# mother_card_10.net
KiCad netlist of a schematic drawn in EAGLE
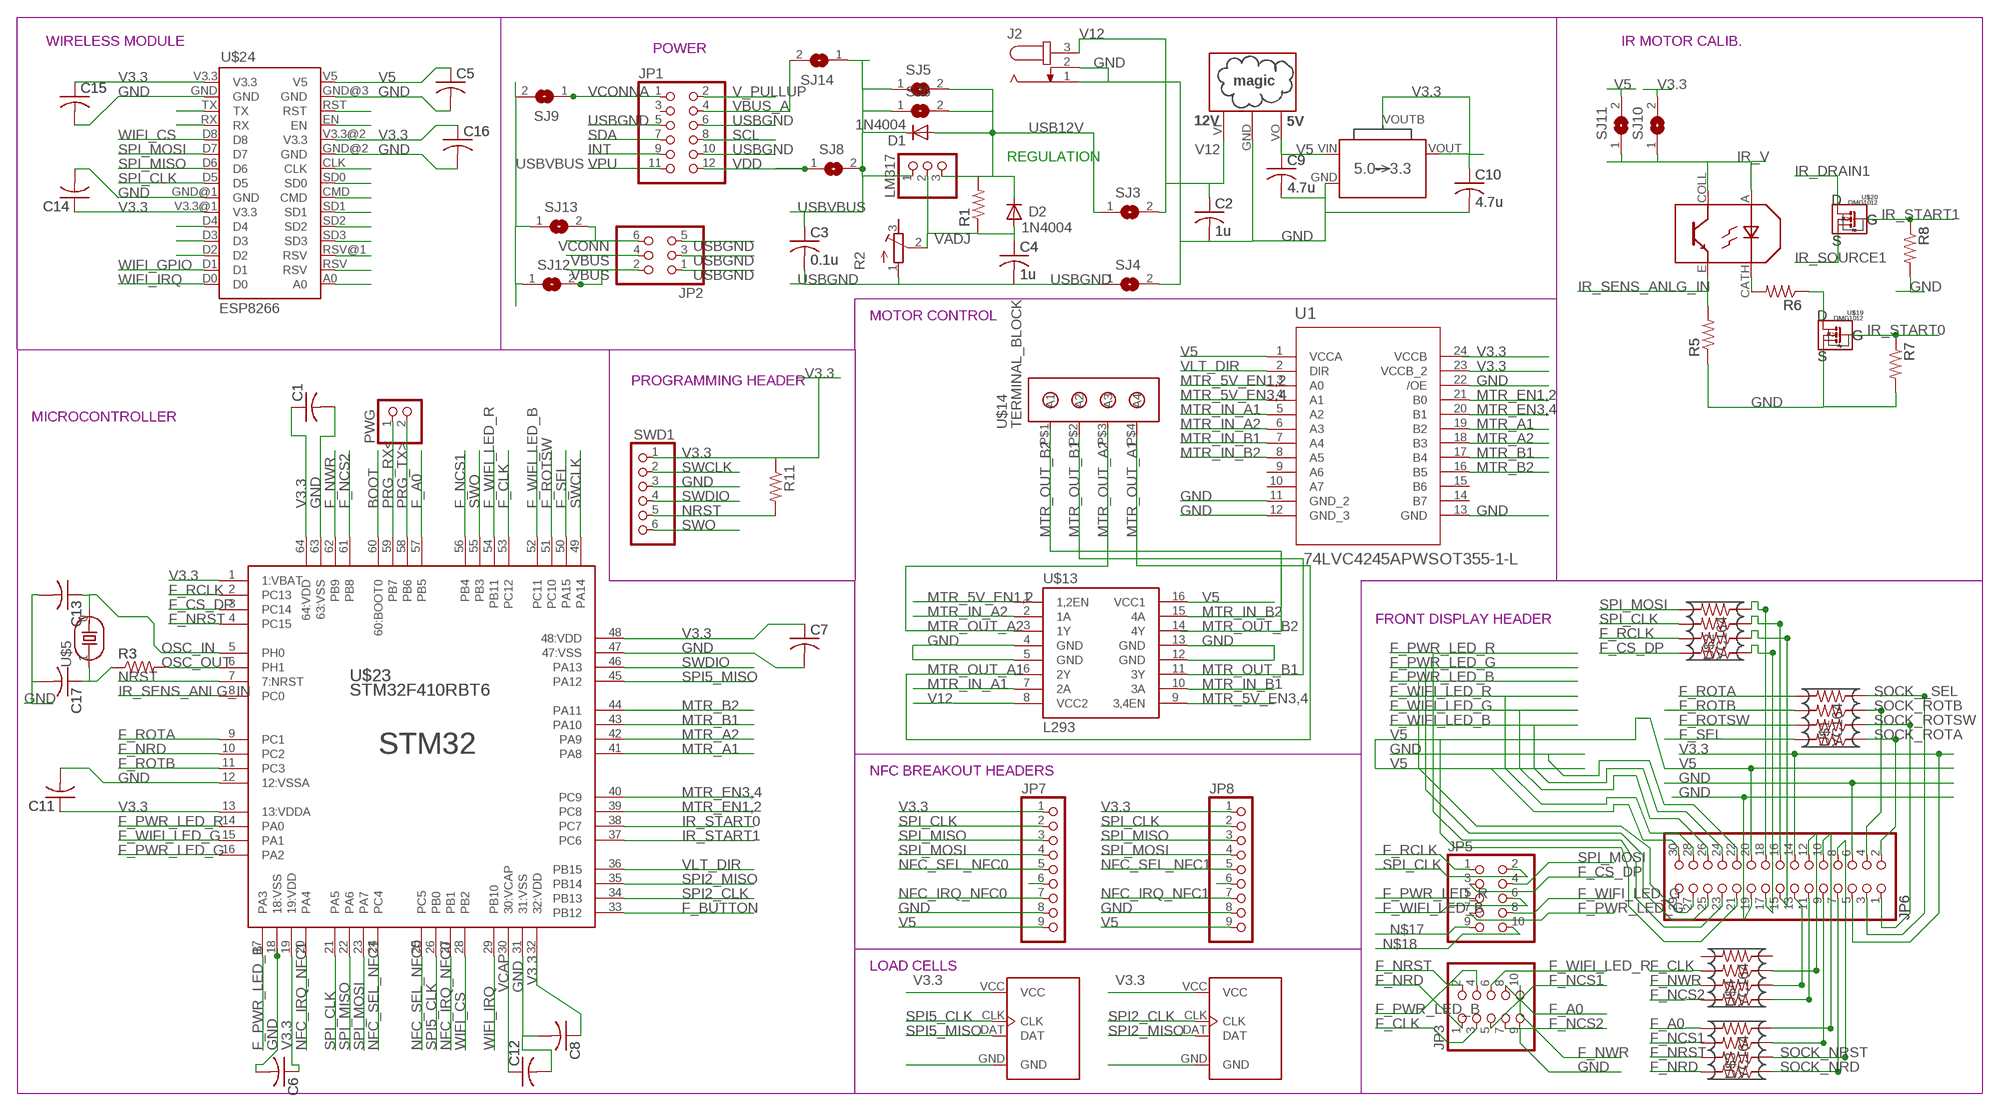
[diagram p0: schematic, sheet 1]

(export (version "E")
  (design (tool "Eeschema 10.0.6"))
  (components
    (comp (ref "C1")
      (value "C-USC0805")
      (footprint "eagle-import:C0805")
      (libsource (lib "eagle-import") (part "C-USC0805"))
    )
    (comp (ref "C2")
      (value "1u")
      (footprint "eagle-import:C0805")
      (libsource (lib "eagle-import") (part "C-USC0805"))
    )
    (comp (ref "C3")
      (value "0.1u")
      (footprint "eagle-import:C0805")
      (libsource (lib "eagle-import") (part "C-USC0805"))
    )
    (comp (ref "C4")
      (value "1u")
      (footprint "eagle-import:C0805")
      (libsource (lib "eagle-import") (part "C-USC0805"))
    )
    (comp (ref "C5")
      (value "C-USC0805")
      (footprint "eagle-import:C0805")
      (libsource (lib "eagle-import") (part "C-USC0805"))
    )
    (comp (ref "C6")
      (value "C-USC0805")
      (footprint "eagle-import:C0805")
      (libsource (lib "eagle-import") (part "C-USC0805"))
    )
    (comp (ref "C7")
      (value "C-USC0805")
      (footprint "eagle-import:C0805")
      (libsource (lib "eagle-import") (part "C-USC0805"))
    )
    (comp (ref "C8")
      (value "C-USC0805")
      (footprint "eagle-import:C0805")
      (libsource (lib "eagle-import") (part "C-USC0805"))
    )
    (comp (ref "C9")
      (value "4.7u")
      (footprint "eagle-import:C0805")
      (libsource (lib "eagle-import") (part "C-USC0805"))
    )
    (comp (ref "C10")
      (value "4.7u")
      (footprint "eagle-import:C0805")
      (libsource (lib "eagle-import") (part "C-USC0805"))
    )
    (comp (ref "C11")
      (value "C-USC0805")
      (footprint "eagle-import:C0805")
      (libsource (lib "eagle-import") (part "C-USC0805"))
    )
    (comp (ref "C12")
      (value "C-USC0805")
      (footprint "eagle-import:C0805")
      (libsource (lib "eagle-import") (part "C-USC0805"))
    )
    (comp (ref "C13")
      (value "C-USC0603")
      (footprint "eagle-import:C0603")
      (libsource (lib "eagle-import") (part "C-USC0603"))
    )
    (comp (ref "C14")
      (value "C-USC0805")
      (footprint "eagle-import:C0805")
      (libsource (lib "eagle-import") (part "C-USC0805"))
    )
    (comp (ref "C15")
      (value "C-USC0805")
      (footprint "eagle-import:C0805")
      (libsource (lib "eagle-import") (part "C-USC0805"))
    )
    (comp (ref "C16")
      (value "C-USC0805")
      (footprint "eagle-import:C0805")
      (libsource (lib "eagle-import") (part "C-USC0805"))
    )
    (comp (ref "C17")
      (value "C-USC0603")
      (footprint "eagle-import:C0603")
      (libsource (lib "eagle-import") (part "C-USC0603"))
    )
    (comp (ref "D1")
      (value "1N4004")
      (footprint "eagle-import:DO41-10")
      (libsource (lib "eagle-import") (part "1N4004"))
    )
    (comp (ref "D2")
      (value "1N4004")
      (footprint "eagle-import:DO41-10")
      (libsource (lib "eagle-import") (part "1N4004"))
    )
    (comp (ref "J2")
      (value "JACK-PLUG0")
      (footprint "eagle-import:SPC4077")
      (libsource (lib "eagle-import") (part "JACK-PLUG0"))
    )
    (comp (ref "JP1")
      (value "PINHD-2X6")
      (footprint "eagle-import:2X06")
      (libsource (lib "eagle-import") (part "PINHD-2X6"))
    )
    (comp (ref "JP2")
      (value "PINHD-2X3")
      (footprint "eagle-import:2X03")
      (libsource (lib "eagle-import") (part "PINHD-2X3"))
    )
    (comp (ref "JP3")
      (value "PINHD-2X5")
      (footprint "eagle-import:2X05")
      (libsource (lib "eagle-import") (part "PINHD-2X5"))
    )
    (comp (ref "JP5")
      (value "PINHD-2X5")
      (footprint "eagle-import:2X05")
      (libsource (lib "eagle-import") (part "PINHD-2X5"))
    )
    (comp (ref "JP6")
      (value "PINHD-2X15/SOCK")
      (footprint "eagle-import:2X15_SOCK")
      (libsource (lib "eagle-import") (part "PINHD-2X15/SOCK"))
    )
    (comp (ref "JP7")
      (value "PINHD-1X9/90")
      (footprint "eagle-import:1X09_90")
      (libsource (lib "eagle-import") (part "PINHD-1X9/90"))
    )
    (comp (ref "JP8")
      (value "PINHD-1X9/90")
      (footprint "eagle-import:1X09_90")
      (libsource (lib "eagle-import") (part "PINHD-1X9/90"))
    )
    (comp (ref "LM317")
      (value "PINHD-1X3")
      (footprint "eagle-import:1X03")
      (libsource (lib "eagle-import") (part "PINHD-1X3"))
    )
    (comp (ref "PWG")
      (value "PINHD-1X2")
      (footprint "eagle-import:1X02")
      (libsource (lib "eagle-import") (part "PINHD-1X2"))
    )
    (comp (ref "R1")
      (value "R-US_R0805")
      (footprint "eagle-import:R0805")
      (libsource (lib "eagle-import") (part "seniorDesign_R-US_R0805"))
    )
    (comp (ref "R2")
      (value "R-TRIMM64W")
      (footprint "eagle-import:RTRIM64W")
      (libsource (lib "eagle-import") (part "R-TRIMM64W"))
    )
    (comp (ref "R3")
      (value "R-US_R0805")
      (footprint "eagle-import:R0805")
      (libsource (lib "eagle-import") (part "seniorDesign_R-US_R0805"))
    )
    (comp (ref "R5")
      (value "R-US_R0805")
      (footprint "eagle-import:R0805")
      (libsource (lib "eagle-import") (part "seniorDesign_R-US_R0805"))
    )
    (comp (ref "R6")
      (value "R-US_R0805")
      (footprint "eagle-import:R0805")
      (libsource (lib "eagle-import") (part "seniorDesign_R-US_R0805"))
    )
    (comp (ref "R7")
      (value "R-US_R0805")
      (footprint "eagle-import:R0805")
      (libsource (lib "eagle-import") (part "seniorDesign_R-US_R0805"))
    )
    (comp (ref "R8")
      (value "R-US_R0805")
      (footprint "eagle-import:R0805")
      (libsource (lib "eagle-import") (part "seniorDesign_R-US_R0805"))
    )
    (comp (ref "R11")
      (value "R-US_R0805")
      (footprint "eagle-import:R0805")
      (libsource (lib "eagle-import") (part "R-US_R0805"))
    )
    (comp (ref "SJ3") (value "SJ") (footprint "eagle-import:SJ") (libsource (lib "eagle-import") (part "SJ")))
    (comp (ref "SJ4") (value "SJ") (footprint "eagle-import:SJ") (libsource (lib "eagle-import") (part "SJ")))
    (comp (ref "SJ5") (value "SJ") (footprint "eagle-import:SJ") (libsource (lib "eagle-import") (part "SJ")))
    (comp (ref "SJ6") (value "SJ") (footprint "eagle-import:SJ") (libsource (lib "eagle-import") (part "SJ")))
    (comp (ref "SJ8") (value "SJ") (footprint "eagle-import:SJ") (libsource (lib "eagle-import") (part "SJ")))
    (comp (ref "SJ9") (value "SJ") (footprint "eagle-import:SJ") (libsource (lib "eagle-import") (part "SJ")))
    (comp (ref "SJ10")
      (value "SJ")
      (footprint "eagle-import:SJ")
      (libsource (lib "eagle-import") (part "SJ"))
    )
    (comp (ref "SJ11")
      (value "SJ")
      (footprint "eagle-import:SJ")
      (libsource (lib "eagle-import") (part "SJ"))
    )
    (comp (ref "SJ12")
      (value "SJ")
      (footprint "eagle-import:SJ")
      (libsource (lib "eagle-import") (part "SJ"))
    )
    (comp (ref "SJ13")
      (value "SJ")
      (footprint "eagle-import:SJ")
      (libsource (lib "eagle-import") (part "SJ"))
    )
    (comp (ref "SJ14")
      (value "SJ")
      (footprint "eagle-import:SJ")
      (libsource (lib "eagle-import") (part "SJ"))
    )
    (comp (ref "SWD1")
      (value "PINHD-1X6")
      (footprint "eagle-import:1X06")
      (libsource (lib "eagle-import") (part "PINHD-1X6"))
    )
    (comp (ref "U$1")
      (value "YC164")
      (footprint "eagle-import:YC164")
      (libsource (lib "eagle-import") (part "YC164"))
    )
    (comp (ref "U$2")
      (value "YC164")
      (footprint "eagle-import:YC164")
      (libsource (lib "eagle-import") (part "YC164"))
    )
    (comp (ref "U$3")
      (value "YC164")
      (footprint "eagle-import:YC164")
      (libsource (lib "eagle-import") (part "YC164"))
    )
    (comp (ref "U$4")
      (value "YC164")
      (footprint "eagle-import:YC164")
      (libsource (lib "eagle-import") (part "YC164"))
    )
    (comp (ref "U$5")
      (value "HC-49S_9B")
      (footprint "eagle-import:HC-49S_9B")
      (libsource (lib "eagle-import") (part "HC-49S_9B"))
    )
    (comp (ref "U$13")
      (value "L293")
      (footprint "eagle-import:DIL16")
      (libsource (lib "eagle-import") (part "L293"))
    )
    (comp (ref "U$14")
      (value "TERMINAL_BLOCK")
      (footprint "eagle-import:1X4_BLOCK")
      (libsource (lib "eagle-import") (part "TERMINAL_BLOCK"))
    )
    (comp (ref "U$15")
      (value "AP2114H")
      (footprint "eagle-import:AP2114H")
      (libsource (lib "eagle-import") (part "AP2114H"))
    )
    (comp (ref "U$16")
      (value "OKI-78SR-W36")
      (footprint "eagle-import:SIP3")
      (libsource (lib "eagle-import") (part "OKI-78SR-W36"))
    )
    (comp (ref "U$18")
      (value "TCRT5000")
      (footprint "eagle-import:TCRT5000")
      (libsource (lib "eagle-import") (part "TCRT5000"))
    )
    (comp (ref "U$19")
      (value "DMG1012")
      (footprint "eagle-import:SOT323")
      (libsource (lib "eagle-import") (part "DMG1012"))
    )
    (comp (ref "U$20")
      (value "DMG1012")
      (footprint "eagle-import:SOT323")
      (libsource (lib "eagle-import") (part "DMG1012"))
    )
    (comp (ref "U$21")
      (value "HX711")
      (footprint "eagle-import:HX711")
      (libsource (lib "eagle-import") (part "HX711"))
    )
    (comp (ref "U$22")
      (value "HX711")
      (footprint "eagle-import:HX711")
      (libsource (lib "eagle-import") (part "HX711"))
    )
    (comp (ref "U$23")
      (value "STM32F410RBT6")
      (footprint "eagle-import:QFP50P1200X1200X160-64N")
      (libsource (lib "eagle-import") (part "STM32F410RBT6"))
    )
    (comp (ref "U$24")
      (value "ESP8266")
      (footprint "eagle-import:ESP8266")
      (libsource (lib "eagle-import") (part "ESP8266"))
    )
    (comp (ref "U1")
      (value "74LVC4245APWSOT355-1-L")
      (footprint "eagle-import:SOT355-1-L")
      (fields (field (name "MANUFACTURER_PART_NUMBER") "74LVC4245APW"))
      (libsource (lib "eagle-import") (part "74LVC4245APWSOT355-1-L"))
    )
  )
  (nets
    (net (code "1") (name "/BOOT") (class "Default")
      (node (ref "U$23") (pin "60") (pinfunction "60:BOOT0_60") (pintype "bidirectional"))
    )
    (net (code "2") (name "/F_A0") (class "Default")
      (node (ref "JP3") (pin "8") (pinfunction "8_8") (pintype "passive"))
      (node (ref "U$23") (pin "57") (pinfunction "PB5_57") (pintype "bidirectional"))
      (node (ref "U$3") (pin "P$4") (pinfunction "4_P$4") (pintype "passive"))
    )
    (net (code "3") (name "/F_BUTTON") (class "Default")
      (node (ref "U$23") (pin "33") (pinfunction "PB12_33") (pintype "bidirectional"))
    )
    (net (code "4") (name "/F_CLK") (class "Default")
      (node (ref "JP3") (pin "3") (pinfunction "3_3") (pintype "passive"))
      (node (ref "U$23") (pin "53") (pinfunction "PC12_53") (pintype "bidirectional"))
      (node (ref "U$4") (pin "P$3") (pinfunction "3_P$3") (pintype "passive"))
    )
    (net (code "5") (name "/F_CS_DP") (class "Default")
      (node (ref "JP5") (pin "3") (pinfunction "3_3") (pintype "passive"))
      (node (ref "U$2") (pin "P$1") (pinfunction "1_P$1") (pintype "passive"))
      (node (ref "U$23") (pin "3") (pinfunction "PC14_3") (pintype "bidirectional"))
    )
    (net (code "6") (name "/F_NCS1") (class "Default")
      (node (ref "JP3") (pin "5") (pinfunction "5_5") (pintype "passive"))
      (node (ref "U$23") (pin "56") (pinfunction "PB4_56") (pintype "bidirectional"))
      (node (ref "U$3") (pin "P$3") (pinfunction "3_P$3") (pintype "passive"))
    )
    (net (code "7") (name "/F_NCS2") (class "Default")
      (node (ref "JP3") (pin "7") (pinfunction "7_7") (pintype "passive"))
      (node (ref "U$23") (pin "61") (pinfunction "PB8_61") (pintype "bidirectional"))
    )
    (net (code "8") (name "/F_NRD") (class "Default")
      (node (ref "JP3") (pin "1") (pinfunction "1_1") (pintype "passive"))
      (node (ref "U$23") (pin "10") (pinfunction "PC2_10") (pintype "bidirectional"))
      (node (ref "U$3") (pin "P$1") (pinfunction "1_P$1") (pintype "passive"))
    )
    (net (code "9") (name "/F_NRST") (class "Default")
      (node (ref "JP3") (pin "2") (pinfunction "2_2") (pintype "passive"))
      (node (ref "U$23") (pin "4") (pinfunction "PC15_4") (pintype "bidirectional"))
      (node (ref "U$3") (pin "P$2") (pinfunction "2_P$2") (pintype "passive"))
    )
    (net (code "10") (name "/F_NWR") (class "Default")
      (node (ref "JP3") (pin "10") (pinfunction "10_10") (pintype "passive"))
      (node (ref "U$23") (pin "62") (pinfunction "PB9_62") (pintype "bidirectional"))
      (node (ref "U$4") (pin "P$2") (pinfunction "2_P$2") (pintype "passive"))
    )
    (net (code "11") (name "/F_PWR_LED_B") (class "Default")
      (node (ref "JP3") (pin "4") (pinfunction "4_4") (pintype "passive"))
      (node (ref "JP6") (pin "27") (pinfunction "27_27") (pintype "passive"))
      (node (ref "U$23") (pin "17") (pinfunction "PA3_17") (pintype "bidirectional"))
    )
    (net (code "12") (name "/F_PWR_LED_G") (class "Default")
      (node (ref "JP5") (pin "7") (pinfunction "7_7") (pintype "passive"))
      (node (ref "JP6") (pin "25") (pinfunction "25_25") (pintype "passive"))
      (node (ref "U$23") (pin "16") (pinfunction "PA2_16") (pintype "bidirectional"))
    )
    (net (code "13") (name "/F_PWR_LED_R") (class "Default")
      (node (ref "JP5") (pin "5") (pinfunction "5_5") (pintype "passive"))
      (node (ref "JP6") (pin "23") (pinfunction "23_23") (pintype "passive"))
      (node (ref "U$23") (pin "14") (pinfunction "PA0_14") (pintype "bidirectional"))
    )
    (net (code "14") (name "/F_RCLK") (class "Default")
      (node (ref "JP5") (pin "1") (pinfunction "1_1") (pintype "passive"))
      (node (ref "U$2") (pin "P$2") (pinfunction "2_P$2") (pintype "passive"))
      (node (ref "U$23") (pin "2") (pinfunction "PC13_2") (pintype "bidirectional"))
    )
    (net (code "15") (name "/F_ROTA") (class "Default")
      (node (ref "U$1") (pin "P$4") (pinfunction "4_P$4") (pintype "passive"))
      (node (ref "U$23") (pin "9") (pinfunction "PC1_9") (pintype "bidirectional"))
    )
    (net (code "16") (name "/F_ROTB") (class "Default")
      (node (ref "U$1") (pin "P$3") (pinfunction "3_P$3") (pintype "passive"))
      (node (ref "U$23") (pin "11") (pinfunction "PC3_11") (pintype "bidirectional"))
    )
    (net (code "17") (name "/F_ROTSW") (class "Default")
      (node (ref "U$1") (pin "P$2") (pinfunction "2_P$2") (pintype "passive"))
      (node (ref "U$23") (pin "51") (pinfunction "PC10_51") (pintype "bidirectional"))
    )
    (net (code "18") (name "/F_SEL") (class "Default")
      (node (ref "U$1") (pin "P$1") (pinfunction "1_P$1") (pintype "passive"))
      (node (ref "U$23") (pin "50") (pinfunction "PA15_50") (pintype "bidirectional"))
    )
    (net (code "19") (name "/F_WIFI_LED_B") (class "Default")
      (node (ref "JP5") (pin "6") (pinfunction "6_6") (pintype "passive"))
      (node (ref "JP6") (pin "24") (pinfunction "24_24") (pintype "passive"))
      (node (ref "U$23") (pin "52") (pinfunction "PC11_52") (pintype "bidirectional"))
    )
    (net (code "20") (name "/F_WIFI_LED_G") (class "Default")
      (node (ref "JP5") (pin "8") (pinfunction "8_8") (pintype "passive"))
      (node (ref "JP6") (pin "26") (pinfunction "26_26") (pintype "passive"))
      (node (ref "U$23") (pin "15") (pinfunction "PA1_15") (pintype "bidirectional"))
    )
    (net (code "21") (name "/F_WIFI_LED_R") (class "Default")
      (node (ref "JP3") (pin "6") (pinfunction "6_6") (pintype "passive"))
      (node (ref "JP6") (pin "28") (pinfunction "28_28") (pintype "passive"))
      (node (ref "U$23") (pin "54") (pinfunction "PB11_54") (pintype "bidirectional"))
    )
    (net (code "22") (name "/GND") (class "Default")
      (node (ref "C1") (pin "2") (pinfunction "2_2") (pintype "passive"))
      (node (ref "C10") (pin "2") (pinfunction "2_2") (pintype "passive"))
      (node (ref "C11") (pin "2") (pinfunction "2_2") (pintype "passive"))
      (node (ref "C12") (pin "2") (pinfunction "2_2") (pintype "passive"))
      (node (ref "C13") (pin "2") (pinfunction "2_2") (pintype "passive"))
      (node (ref "C14") (pin "2") (pinfunction "2_2") (pintype "passive"))
      (node (ref "C15") (pin "2") (pinfunction "2_2") (pintype "passive"))
      (node (ref "C16") (pin "2") (pinfunction "2_2") (pintype "passive"))
      (node (ref "C17") (pin "2") (pinfunction "2_2") (pintype "passive"))
      (node (ref "C2") (pin "2") (pinfunction "2_2") (pintype "passive"))
      (node (ref "C5") (pin "2") (pinfunction "2_2") (pintype "passive"))
      (node (ref "C6") (pin "2") (pinfunction "2_2") (pintype "passive"))
      (node (ref "C7") (pin "2") (pinfunction "2_2") (pintype "passive"))
      (node (ref "C8") (pin "2") (pinfunction "2_2") (pintype "passive"))
      (node (ref "C9") (pin "2") (pinfunction "2_2") (pintype "passive"))
      (node (ref "J2") (pin "1") (pinfunction "1_1") (pintype "passive"))
      (node (ref "J2") (pin "2") (pinfunction "2_2") (pintype "passive"))
      (node (ref "JP3") (pin "9") (pinfunction "9_9") (pintype "passive"))
      (node (ref "JP6") (pin "19") (pinfunction "19_19") (pintype "passive"))
      (node (ref "JP6") (pin "22") (pinfunction "22_22") (pintype "passive"))
      (node (ref "JP6") (pin "6") (pinfunction "6_6") (pintype "passive"))
      (node (ref "JP7") (pin "8") (pinfunction "8_8") (pintype "passive"))
      (node (ref "JP8") (pin "8") (pinfunction "8_8") (pintype "passive"))
      (node (ref "R5") (pin "1") (pinfunction "1_1") (pintype "passive"))
      (node (ref "R7") (pin "2") (pinfunction "2_2") (pintype "passive"))
      (node (ref "R8") (pin "2") (pinfunction "2_2") (pintype "passive"))
      (node (ref "SJ4") (pin "2") (pinfunction "2_2") (pintype "passive"))
      (node (ref "SWD1") (pin "3") (pinfunction "3_3") (pintype "passive"))
      (node (ref "U$13") (pin "12") (pinfunction "GND_12") (pintype "bidirectional"))
      (node (ref "U$13") (pin "13") (pinfunction "GND_13") (pintype "bidirectional"))
      (node (ref "U$13") (pin "4") (pinfunction "GND_4") (pintype "bidirectional"))
      (node (ref "U$13") (pin "5") (pinfunction "GND_5") (pintype "bidirectional"))
      (node (ref "U$15") (pin "GND") (pinfunction "GND_GND") (pintype "power_in"))
      (node (ref "U$16") (pin "GND") (pinfunction "P$2_GND") (pintype "power_in"))
      (node (ref "U$19") (pin "S") (pinfunction "S_S") (pintype "bidirectional"))
      (node (ref "U$21") (pin "GND") (pinfunction "GND_GND") (pintype "power_in"))
      (node (ref "U$22") (pin "GND") (pinfunction "GND_GND") (pintype "power_in"))
      (node (ref "U$23") (pin "12") (pinfunction "12:VSSA_12") (pintype "bidirectional"))
      (node (ref "U$23") (pin "18") (pinfunction "18:VSS_18") (pintype "bidirectional"))
      (node (ref "U$23") (pin "31") (pinfunction "31:VSS_31") (pintype "bidirectional"))
      (node (ref "U$23") (pin "47") (pinfunction "47:VSS_47") (pintype "bidirectional"))
      (node (ref "U$23") (pin "63") (pinfunction "63:VSS_63") (pintype "bidirectional"))
      (node (ref "U$24") (pin "GND") (pinfunction "GND_GND") (pintype "bidirectional"))
      (node (ref "U$24") (pin "GND@1") (pinfunction "GND_GND@1") (pintype "bidirectional"))
      (node (ref "U$24") (pin "GND@2") (pinfunction "GND_GND@2") (pintype "bidirectional"))
      (node (ref "U$24") (pin "GND@3") (pinfunction "GND_GND@3") (pintype "bidirectional"))
      (node (ref "U1") (pin "11") (pinfunction "GND_2_11") (pintype "power_in"))
      (node (ref "U1") (pin "12") (pinfunction "GND_3_12") (pintype "power_in"))
      (node (ref "U1") (pin "13") (pinfunction "GND_13") (pintype "power_in"))
      (node (ref "U1") (pin "22") (pinfunction "/OE_22") (pintype "input"))
    )
    (net (code "23") (name "/INT") (class "Default")
      (node (ref "JP1") (pin "9") (pinfunction "9_9") (pintype "passive"))
    )
    (net (code "24") (name "/IR_DRAIN1") (class "Default")
      (node (ref "U$20") (pin "D") (pinfunction "D_D") (pintype "bidirectional"))
    )
    (net (code "25") (name "/IR_SENS_ANLG_IN") (class "Default")
      (node (ref "R5") (pin "2") (pinfunction "2_2") (pintype "passive"))
      (node (ref "U$18") (pin "E") (pinfunction "E_E") (pintype "bidirectional"))
      (node (ref "U$23") (pin "8") (pinfunction "PC0_8") (pintype "bidirectional"))
    )
    (net (code "26") (name "/IR_SOURCE1") (class "Default")
      (node (ref "U$20") (pin "S") (pinfunction "S_S") (pintype "bidirectional"))
    )
    (net (code "27") (name "/IR_START0") (class "Default")
      (node (ref "R7") (pin "1") (pinfunction "1_1") (pintype "passive"))
      (node (ref "U$19") (pin "G") (pinfunction "G_G") (pintype "bidirectional"))
      (node (ref "U$23") (pin "38") (pinfunction "PC7_38") (pintype "bidirectional"))
    )
    (net (code "28") (name "/IR_START1") (class "Default")
      (node (ref "R8") (pin "1") (pinfunction "1_1") (pintype "passive"))
      (node (ref "U$20") (pin "G") (pinfunction "G_G") (pintype "bidirectional"))
      (node (ref "U$23") (pin "37") (pinfunction "PC6_37") (pintype "bidirectional"))
    )
    (net (code "29") (name "/IR_V") (class "Default")
      (node (ref "SJ10") (pin "1") (pinfunction "1_1") (pintype "passive"))
      (node (ref "SJ11") (pin "1") (pinfunction "1_1") (pintype "passive"))
      (node (ref "U$18") (pin "A") (pinfunction "A_A") (pintype "bidirectional"))
      (node (ref "U$18") (pin "COLL") (pinfunction "COLL_COLL") (pintype "bidirectional"))
    )
    (net (code "30") (name "/MTR_5V_EN1,2") (class "Default")
      (node (ref "U$13") (pin "1") (pinfunction "1,2EN_1") (pintype "bidirectional"))
      (node (ref "U1") (pin "3") (pinfunction "A0_3") (pintype "bidirectional"))
    )
    (net (code "31") (name "/MTR_5V_EN3,4") (class "Default")
      (node (ref "U$13") (pin "9") (pinfunction "3,4EN_9") (pintype "bidirectional"))
      (node (ref "U1") (pin "4") (pinfunction "A1_4") (pintype "bidirectional"))
    )
    (net (code "32") (name "/MTR_A1") (class "Default")
      (node (ref "U$23") (pin "41") (pinfunction "PA8_41") (pintype "bidirectional"))
      (node (ref "U1") (pin "19") (pinfunction "B2_19") (pintype "bidirectional"))
    )
    (net (code "33") (name "/MTR_A2") (class "Default")
      (node (ref "U$23") (pin "42") (pinfunction "PA9_42") (pintype "bidirectional"))
      (node (ref "U1") (pin "18") (pinfunction "B3_18") (pintype "bidirectional"))
    )
    (net (code "34") (name "/MTR_B1") (class "Default")
      (node (ref "U$23") (pin "43") (pinfunction "PA10_43") (pintype "bidirectional"))
      (node (ref "U1") (pin "17") (pinfunction "B4_17") (pintype "bidirectional"))
    )
    (net (code "35") (name "/MTR_B2") (class "Default")
      (node (ref "U$23") (pin "44") (pinfunction "PA11_44") (pintype "bidirectional"))
      (node (ref "U1") (pin "16") (pinfunction "B5_16") (pintype "bidirectional"))
    )
    (net (code "36") (name "/MTR_EN1,2") (class "Default")
      (node (ref "U$23") (pin "39") (pinfunction "PC8_39") (pintype "bidirectional"))
      (node (ref "U1") (pin "21") (pinfunction "B0_21") (pintype "bidirectional"))
    )
    (net (code "37") (name "/MTR_EN3,4") (class "Default")
      (node (ref "U$23") (pin "40") (pinfunction "PC9_40") (pintype "bidirectional"))
      (node (ref "U1") (pin "20") (pinfunction "B1_20") (pintype "bidirectional"))
    )
    (net (code "38") (name "/MTR_IN_A1") (class "Default")
      (node (ref "U$13") (pin "7") (pinfunction "2A_7") (pintype "bidirectional"))
      (node (ref "U1") (pin "5") (pinfunction "A2_5") (pintype "bidirectional"))
    )
    (net (code "39") (name "/MTR_IN_A2") (class "Default")
      (node (ref "U$13") (pin "2") (pinfunction "1A_2") (pintype "bidirectional"))
      (node (ref "U1") (pin "6") (pinfunction "A3_6") (pintype "bidirectional"))
    )
    (net (code "40") (name "/MTR_IN_B1") (class "Default")
      (node (ref "U$13") (pin "10") (pinfunction "3A_10") (pintype "bidirectional"))
      (node (ref "U1") (pin "7") (pinfunction "A4_7") (pintype "bidirectional"))
    )
    (net (code "41") (name "/MTR_IN_B2") (class "Default")
      (node (ref "U$13") (pin "15") (pinfunction "4A_15") (pintype "bidirectional"))
      (node (ref "U1") (pin "8") (pinfunction "A5_8") (pintype "bidirectional"))
    )
    (net (code "42") (name "/MTR_OUT_A1") (class "Default")
      (node (ref "U$13") (pin "6") (pinfunction "2Y_6") (pintype "bidirectional"))
      (node (ref "U$14") (pin "P$4") (pinfunction "A4_P$4") (pintype "bidirectional"))
    )
    (net (code "43") (name "/MTR_OUT_A2") (class "Default")
      (node (ref "U$13") (pin "3") (pinfunction "1Y_3") (pintype "bidirectional"))
      (node (ref "U$14") (pin "P$3") (pinfunction "A3_P$3") (pintype "bidirectional"))
    )
    (net (code "44") (name "/MTR_OUT_B1") (class "Default")
      (node (ref "U$13") (pin "11") (pinfunction "3Y_11") (pintype "bidirectional"))
      (node (ref "U$14") (pin "P$2") (pinfunction "A2_P$2") (pintype "bidirectional"))
    )
    (net (code "45") (name "/MTR_OUT_B2") (class "Default")
      (node (ref "U$13") (pin "14") (pinfunction "4Y_14") (pintype "bidirectional"))
      (node (ref "U$14") (pin "P$1") (pinfunction "A1_P$1") (pintype "bidirectional"))
    )
    (net (code "46") (name "/N$17") (class "Default")
      (node (ref "JP5") (pin "9") (pinfunction "9_9") (pintype "passive"))
    )
    (net (code "47") (name "/N$18") (class "Default")
      (node (ref "JP5") (pin "10") (pinfunction "10_10") (pintype "passive"))
    )
    (net (code "48") (name "/NFC_IRQ_NFC0") (class "Default")
      (node (ref "JP7") (pin "7") (pinfunction "7_7") (pintype "passive"))
      (node (ref "U$23") (pin "27") (pinfunction "PB1_27") (pintype "bidirectional"))
    )
    (net (code "49") (name "/NFC_IRQ_NFC1") (class "Default")
      (node (ref "JP8") (pin "7") (pinfunction "7_7") (pintype "passive"))
      (node (ref "U$23") (pin "20") (pinfunction "PA4_20") (pintype "bidirectional"))
    )
    (net (code "50") (name "/NFC_SEL_NFC0") (class "Default")
      (node (ref "JP7") (pin "5") (pinfunction "5_5") (pintype "passive"))
      (node (ref "U$23") (pin "25") (pinfunction "PC5_25") (pintype "bidirectional"))
    )
    (net (code "51") (name "/NFC_SEL_NFC1") (class "Default")
      (node (ref "JP8") (pin "5") (pinfunction "5_5") (pintype "passive"))
      (node (ref "U$23") (pin "24") (pinfunction "PC4_24") (pintype "bidirectional"))
    )
    (net (code "52") (name "/NRST") (class "Default")
      (node (ref "R11") (pin "2") (pinfunction "2_2") (pintype "passive"))
      (node (ref "SWD1") (pin "5") (pinfunction "5_5") (pintype "passive"))
      (node (ref "U$23") (pin "7") (pinfunction "7:NRST_7") (pintype "bidirectional"))
    )
    (net (code "53") (name "/OSC_IN") (class "Default")
      (node (ref "C13") (pin "1") (pinfunction "1_1") (pintype "passive"))
      (node (ref "U$23") (pin "5") (pinfunction "PH0_5") (pintype "bidirectional"))
      (node (ref "U$5") (pin "0") (pinfunction "P$1_0") (pintype "bidirectional"))
    )
    (net (code "54") (name "/OSC_OUT") (class "Default")
      (node (ref "C17") (pin "1") (pinfunction "1_1") (pintype "passive"))
      (node (ref "R3") (pin "1") (pinfunction "1_1") (pintype "passive"))
      (node (ref "U$5") (pin "1") (pinfunction "P$2_1") (pintype "bidirectional"))
    )
    (net (code "55") (name "/PRG_RX<") (class "Default")
      (node (ref "PWG") (pin "1") (pinfunction "1_1") (pintype "passive"))
      (node (ref "U$23") (pin "59") (pinfunction "PB7_59") (pintype "bidirectional"))
    )
    (net (code "56") (name "/PRG_TX>") (class "Default")
      (node (ref "PWG") (pin "2") (pinfunction "2_2") (pintype "passive"))
      (node (ref "U$23") (pin "58") (pinfunction "PB6_58") (pintype "bidirectional"))
    )
    (net (code "57") (name "/SCL") (class "Default")
      (node (ref "JP1") (pin "8") (pinfunction "8_8") (pintype "passive"))
    )
    (net (code "58") (name "/SDA") (class "Default")
      (node (ref "JP1") (pin "7") (pinfunction "7_7") (pintype "passive"))
    )
    (net (code "59") (name "/SOCK_NRD") (class "Default")
      (node (ref "JP6") (pin "7") (pinfunction "7_7") (pintype "passive"))
      (node (ref "U$3") (pin "P$11") (pinfunction "11_P$11") (pintype "passive"))
    )
    (net (code "60") (name "/SOCK_NRST") (class "Default")
      (node (ref "JP6") (pin "8") (pinfunction "8_8") (pintype "passive"))
      (node (ref "U$3") (pin "P$22") (pinfunction "22_P$22") (pintype "passive"))
    )
    (net (code "61") (name "/SOCK_ROTA") (class "Default")
      (node (ref "JP6") (pin "2") (pinfunction "2_2") (pintype "passive"))
      (node (ref "U$1") (pin "P$11") (pinfunction "11_P$11") (pintype "passive"))
    )
    (net (code "62") (name "/SOCK_ROTB") (class "Default")
      (node (ref "JP6") (pin "4") (pinfunction "4_4") (pintype "passive"))
      (node (ref "U$1") (pin "P$33") (pinfunction "33_P$33") (pintype "passive"))
    )
    (net (code "63") (name "/SOCK_ROTSW") (class "Default")
      (node (ref "JP6") (pin "1") (pinfunction "1_1") (pintype "passive"))
      (node (ref "U$1") (pin "P$22") (pinfunction "22_P$22") (pintype "passive"))
    )
    (net (code "64") (name "/SOCK__SEL") (class "Default")
      (node (ref "JP6") (pin "3") (pinfunction "3_3") (pintype "passive"))
      (node (ref "U$1") (pin "P$44") (pinfunction "44_P$44") (pintype "passive"))
    )
    (net (code "65") (name "/SPI2_CLK") (class "Default")
      (node (ref "U$22") (pin "CLK") (pinfunction "CLK_CLK") (pintype "bidirectional"))
      (node (ref "U$23") (pin "34") (pinfunction "PB13_34") (pintype "bidirectional"))
    )
    (net (code "66") (name "/SPI2_MISO") (class "Default")
      (node (ref "U$22") (pin "DAT") (pinfunction "DAT_DAT") (pintype "bidirectional"))
      (node (ref "U$23") (pin "35") (pinfunction "PB14_35") (pintype "bidirectional"))
    )
    (net (code "67") (name "/SPI5_CLK") (class "Default")
      (node (ref "U$21") (pin "CLK") (pinfunction "CLK_CLK") (pintype "bidirectional"))
      (node (ref "U$23") (pin "26") (pinfunction "PB0_26") (pintype "bidirectional"))
    )
    (net (code "68") (name "/SPI5_MISO") (class "Default")
      (node (ref "U$21") (pin "DAT") (pinfunction "DAT_DAT") (pintype "bidirectional"))
      (node (ref "U$23") (pin "45") (pinfunction "PA12_45") (pintype "bidirectional"))
    )
    (net (code "69") (name "/SPI_CLK") (class "Default")
      (node (ref "JP5") (pin "2") (pinfunction "2_2") (pintype "passive"))
      (node (ref "JP7") (pin "2") (pinfunction "2_2") (pintype "passive"))
      (node (ref "JP8") (pin "2") (pinfunction "2_2") (pintype "passive"))
      (node (ref "U$2") (pin "P$3") (pinfunction "3_P$3") (pintype "passive"))
      (node (ref "U$23") (pin "21") (pinfunction "PA5_21") (pintype "bidirectional"))
      (node (ref "U$24") (pin "D5") (pinfunction "D5_D5") (pintype "bidirectional"))
    )
    (net (code "70") (name "/SPI_MISO") (class "Default")
      (node (ref "JP7") (pin "3") (pinfunction "3_3") (pintype "passive"))
      (node (ref "JP8") (pin "3") (pinfunction "3_3") (pintype "passive"))
      (node (ref "U$23") (pin "22") (pinfunction "PA6_22") (pintype "bidirectional"))
      (node (ref "U$24") (pin "D6") (pinfunction "D6_D6") (pintype "bidirectional"))
    )
    (net (code "71") (name "/SPI_MOSI") (class "Default")
      (node (ref "JP5") (pin "4") (pinfunction "4_4") (pintype "passive"))
      (node (ref "JP7") (pin "4") (pinfunction "4_4") (pintype "passive"))
      (node (ref "JP8") (pin "4") (pinfunction "4_4") (pintype "passive"))
      (node (ref "U$2") (pin "P$4") (pinfunction "4_P$4") (pintype "passive"))
      (node (ref "U$23") (pin "23") (pinfunction "PA7_23") (pintype "bidirectional"))
      (node (ref "U$24") (pin "D7") (pinfunction "D7_D7") (pintype "bidirectional"))
    )
    (net (code "72") (name "/SWCLK") (class "Default")
      (node (ref "SWD1") (pin "2") (pinfunction "2_2") (pintype "passive"))
      (node (ref "U$23") (pin "49") (pinfunction "PA14_49") (pintype "bidirectional"))
    )
    (net (code "73") (name "/SWDIO") (class "Default")
      (node (ref "SWD1") (pin "4") (pinfunction "4_4") (pintype "passive"))
      (node (ref "U$23") (pin "46") (pinfunction "PA13_46") (pintype "bidirectional"))
    )
    (net (code "74") (name "/SWO") (class "Default")
      (node (ref "SWD1") (pin "6") (pinfunction "6_6") (pintype "passive"))
      (node (ref "U$23") (pin "55") (pinfunction "PB3_55") (pintype "bidirectional"))
    )
    (net (code "75") (name "/USB12V") (class "Default")
      (node (ref "D1") (pin "A") (pinfunction "A_A") (pintype "passive"))
      (node (ref "D2") (pin "C") (pinfunction "C_C") (pintype "passive"))
      (node (ref "LM317") (pin "3") (pinfunction "3_3") (pintype "passive"))
      (node (ref "R1") (pin "2") (pinfunction "2_2") (pintype "passive"))
      (node (ref "SJ3") (pin "1") (pinfunction "1_1") (pintype "passive"))
      (node (ref "SJ5") (pin "2") (pinfunction "2_2") (pintype "passive"))
      (node (ref "SJ6") (pin "2") (pinfunction "2_2") (pintype "passive"))
    )
    (net (code "76") (name "/USBGND") (class "Default")
      (node (ref "C3") (pin "2") (pinfunction "2_2") (pintype "passive"))
      (node (ref "C4") (pin "2") (pinfunction "2_2") (pintype "passive"))
      (node (ref "JP1") (pin "10") (pinfunction "10_10") (pintype "passive"))
      (node (ref "JP1") (pin "5") (pinfunction "5_5") (pintype "passive"))
      (node (ref "JP1") (pin "6") (pinfunction "6_6") (pintype "passive"))
      (node (ref "JP2") (pin "1") (pinfunction "1_1") (pintype "passive"))
      (node (ref "JP2") (pin "3") (pinfunction "3_3") (pintype "passive"))
      (node (ref "JP2") (pin "5") (pinfunction "5_5") (pintype "passive"))
      (node (ref "R2") (pin "1") (pinfunction "A_1") (pintype "passive"))
      (node (ref "SJ4") (pin "1") (pinfunction "1_1") (pintype "passive"))
    )
    (net (code "77") (name "/USBVBUS") (class "Default")
      (node (ref "C3") (pin "1") (pinfunction "1_1") (pintype "passive"))
      (node (ref "D1") (pin "C") (pinfunction "C_C") (pintype "passive"))
      (node (ref "LM317") (pin "1") (pinfunction "1_1") (pintype "passive"))
      (node (ref "SJ12") (pin "1") (pinfunction "1_1") (pintype "passive"))
      (node (ref "SJ13") (pin "1") (pinfunction "1_1") (pintype "passive"))
      (node (ref "SJ14") (pin "1") (pinfunction "1_1") (pintype "passive"))
      (node (ref "SJ5") (pin "1") (pinfunction "1_1") (pintype "passive"))
      (node (ref "SJ6") (pin "1") (pinfunction "1_1") (pintype "passive"))
      (node (ref "SJ8") (pin "2") (pinfunction "2_2") (pintype "passive"))
      (node (ref "SJ9") (pin "2") (pinfunction "2_2") (pintype "passive"))
    )
    (net (code "78") (name "/V3.3") (class "Default")
      (node (ref "C1") (pin "1") (pinfunction "1_1") (pintype "passive"))
      (node (ref "C10") (pin "1") (pinfunction "1_1") (pintype "passive"))
      (node (ref "C11") (pin "1") (pinfunction "1_1") (pintype "passive"))
      (node (ref "C14") (pin "1") (pinfunction "1_1") (pintype "passive"))
      (node (ref "C15") (pin "1") (pinfunction "1_1") (pintype "passive"))
      (node (ref "C16") (pin "1") (pinfunction "1_1") (pintype "passive"))
      (node (ref "C6") (pin "1") (pinfunction "1_1") (pintype "passive"))
      (node (ref "C7") (pin "1") (pinfunction "1_1") (pintype "passive"))
      (node (ref "C8") (pin "1") (pinfunction "1_1") (pintype "passive"))
      (node (ref "JP6") (pin "14") (pinfunction "14_14") (pintype "passive"))
      (node (ref "JP6") (pin "5") (pinfunction "5_5") (pintype "passive"))
      (node (ref "JP7") (pin "1") (pinfunction "1_1") (pintype "passive"))
      (node (ref "JP8") (pin "1") (pinfunction "1_1") (pintype "passive"))
      (node (ref "R11") (pin "1") (pinfunction "1_1") (pintype "passive"))
      (node (ref "SJ10") (pin "2") (pinfunction "2_2") (pintype "passive"))
      (node (ref "SWD1") (pin "1") (pinfunction "1_1") (pintype "passive"))
      (node (ref "U$15") (pin "VOUT") (pinfunction "VO_VOUT") (pintype "output"))
      (node (ref "U$15") (pin "VOUTB") (pinfunction "BODY_VOUTB") (pintype "open_collector"))
      (node (ref "U$21") (pin "VCC") (pinfunction "VCC_VCC") (pintype "power_in"))
      (node (ref "U$22") (pin "VCC") (pinfunction "VCC_VCC") (pintype "power_in"))
      (node (ref "U$23") (pin "1") (pinfunction "1:VBAT_1") (pintype "bidirectional"))
      (node (ref "U$23") (pin "13") (pinfunction "13:VDDA_13") (pintype "bidirectional"))
      (node (ref "U$23") (pin "19") (pinfunction "19:VDD_19") (pintype "bidirectional"))
      (node (ref "U$23") (pin "32") (pinfunction "32:VDD_32") (pintype "bidirectional"))
      (node (ref "U$23") (pin "48") (pinfunction "48:VDD_48") (pintype "bidirectional"))
      (node (ref "U$23") (pin "64") (pinfunction "64:VDD_64") (pintype "bidirectional"))
      (node (ref "U$24") (pin "V3.3") (pinfunction "V3.3_V3.3") (pintype "bidirectional"))
      (node (ref "U$24") (pin "V3.3@1") (pinfunction "V3.3_V3.3@1") (pintype "bidirectional"))
      (node (ref "U$24") (pin "V3.3@2") (pinfunction "V3.3_V3.3@2") (pintype "bidirectional"))
      (node (ref "U1") (pin "23") (pinfunction "VCCB_2_23") (pintype "power_in"))
      (node (ref "U1") (pin "24") (pinfunction "VCCB_24") (pintype "power_in"))
    )
    (net (code "79") (name "/V5") (class "Default")
      (node (ref "C5") (pin "1") (pinfunction "1_1") (pintype "passive"))
      (node (ref "C9") (pin "1") (pinfunction "1_1") (pintype "passive"))
      (node (ref "JP6") (pin "20") (pinfunction "20_20") (pintype "passive"))
      (node (ref "JP6") (pin "21") (pinfunction "21_21") (pintype "passive"))
      (node (ref "JP6") (pin "30") (pinfunction "30_30") (pintype "passive"))
      (node (ref "JP7") (pin "9") (pinfunction "9_9") (pintype "passive"))
      (node (ref "JP8") (pin "9") (pinfunction "9_9") (pintype "passive"))
      (node (ref "SJ11") (pin "2") (pinfunction "2_2") (pintype "passive"))
      (node (ref "U$13") (pin "16") (pinfunction "VCC1_16") (pintype "bidirectional"))
      (node (ref "U$15") (pin "VIN") (pinfunction "VI_VIN") (pintype "input"))
      (node (ref "U$16") (pin "VO") (pinfunction "P$3_VO") (pintype "output"))
      (node (ref "U$24") (pin "V5") (pinfunction "V5_V5") (pintype "bidirectional"))
      (node (ref "U1") (pin "1") (pinfunction "VCCA_1") (pintype "power_in"))
    )
    (net (code "80") (name "/V12") (class "Default")
      (node (ref "C2") (pin "1") (pinfunction "1_1") (pintype "passive"))
      (node (ref "J2") (pin "3") (pinfunction "3_3") (pintype "passive"))
      (node (ref "SJ3") (pin "2") (pinfunction "2_2") (pintype "passive"))
      (node (ref "U$13") (pin "8") (pinfunction "VCC2_8") (pintype "bidirectional"))
      (node (ref "U$16") (pin "VI") (pinfunction "P$1_VI") (pintype "input"))
    )
    (net (code "81") (name "/VADJ") (class "Default")
      (node (ref "C4") (pin "1") (pinfunction "1_1") (pintype "passive"))
      (node (ref "D2") (pin "A") (pinfunction "A_A") (pintype "passive"))
      (node (ref "LM317") (pin "2") (pinfunction "2_2") (pintype "passive"))
      (node (ref "R1") (pin "1") (pinfunction "1_1") (pintype "passive"))
      (node (ref "R2") (pin "2") (pinfunction "S_2") (pintype "passive"))
    )
    (net (code "82") (name "/VBUS") (class "Default")
      (node (ref "JP2") (pin "2") (pinfunction "2_2") (pintype "passive"))
      (node (ref "JP2") (pin "4") (pinfunction "4_4") (pintype "passive"))
      (node (ref "SJ12") (pin "2") (pinfunction "2_2") (pintype "passive"))
    )
    (net (code "83") (name "/VBUS_A") (class "Default")
      (node (ref "JP1") (pin "4") (pinfunction "4_4") (pintype "passive"))
      (node (ref "SJ14") (pin "2") (pinfunction "2_2") (pintype "passive"))
    )
    (net (code "84") (name "/VCAP") (class "Default")
      (node (ref "C12") (pin "1") (pinfunction "1_1") (pintype "passive"))
      (node (ref "U$23") (pin "30") (pinfunction "30:VCAP_30") (pintype "bidirectional"))
    )
    (net (code "85") (name "/VCONN") (class "Default")
      (node (ref "JP2") (pin "6") (pinfunction "6_6") (pintype "passive"))
      (node (ref "SJ13") (pin "2") (pinfunction "2_2") (pintype "passive"))
    )
    (net (code "86") (name "/VCONNA") (class "Default")
      (node (ref "JP1") (pin "1") (pinfunction "1_1") (pintype "passive"))
      (node (ref "SJ9") (pin "1") (pinfunction "1_1") (pintype "passive"))
    )
    (net (code "87") (name "/VDD") (class "Default")
      (node (ref "JP1") (pin "12") (pinfunction "12_12") (pintype "passive"))
      (node (ref "SJ8") (pin "1") (pinfunction "1_1") (pintype "passive"))
    )
    (net (code "88") (name "/VLT_DIR") (class "Default")
      (node (ref "U$23") (pin "36") (pinfunction "PB15_36") (pintype "bidirectional"))
      (node (ref "U1") (pin "2") (pinfunction "DIR_2") (pintype "input"))
    )
    (net (code "89") (name "/VPU") (class "Default")
      (node (ref "JP1") (pin "11") (pinfunction "11_11") (pintype "passive"))
    )
    (net (code "90") (name "/V_PULLUP") (class "Default")
      (node (ref "JP1") (pin "2") (pinfunction "2_2") (pintype "passive"))
    )
    (net (code "91") (name "/WIFI_CS") (class "Default")
      (node (ref "U$23") (pin "28") (pinfunction "PB2_28") (pintype "bidirectional"))
      (node (ref "U$24") (pin "D8") (pinfunction "D8_D8") (pintype "bidirectional"))
    )
    (net (code "92") (name "/WIFI_GPIO") (class "Default")
      (node (ref "U$24") (pin "D1") (pinfunction "D1_D1") (pintype "bidirectional"))
    )
    (net (code "93") (name "/WIFI_IRQ") (class "Default")
      (node (ref "U$23") (pin "29") (pinfunction "PB10_29") (pintype "bidirectional"))
      (node (ref "U$24") (pin "D0") (pinfunction "D0_D0") (pintype "bidirectional"))
    )
    (net (code "94") (name "Net-(R6-Pad1)") (class "Default")
      (node (ref "R6") (pin "1") (pinfunction "1_1") (pintype "passive"))
      (node (ref "U$19") (pin "D") (pinfunction "D_D") (pintype "bidirectional"))
    )
    (net (code "95") (name "Net-(R6-Pad2)") (class "Default")
      (node (ref "R6") (pin "2") (pinfunction "2_2") (pintype "passive"))
      (node (ref "U$18") (pin "CATH") (pinfunction "CATH_CATH") (pintype "bidirectional"))
    )
    (net (code "96") (name "Net-(U$2-11)") (class "Default")
      (node (ref "JP6") (pin "17") (pinfunction "17_17") (pintype "passive"))
      (node (ref "U$2") (pin "P$11") (pinfunction "11_P$11") (pintype "passive"))
    )
    (net (code "97") (name "Net-(U$2-22)") (class "Default")
      (node (ref "JP6") (pin "15") (pinfunction "15_15") (pintype "passive"))
      (node (ref "U$2") (pin "P$22") (pinfunction "22_P$22") (pintype "passive"))
    )
    (net (code "98") (name "Net-(U$2-33)") (class "Default")
      (node (ref "JP6") (pin "16") (pinfunction "16_16") (pintype "passive"))
      (node (ref "U$2") (pin "P$33") (pinfunction "33_P$33") (pintype "passive"))
    )
    (net (code "99") (name "Net-(U$2-44)") (class "Default")
      (node (ref "JP6") (pin "18") (pinfunction "18_18") (pintype "passive"))
      (node (ref "U$2") (pin "P$44") (pinfunction "44_P$44") (pintype "passive"))
    )
    (net (code "100") (name "Net-(U$3-33)") (class "Default")
      (node (ref "JP6") (pin "9") (pinfunction "9_9") (pintype "passive"))
      (node (ref "U$3") (pin "P$33") (pinfunction "33_P$33") (pintype "passive"))
    )
    (net (code "101") (name "Net-(U$3-44)") (class "Default")
      (node (ref "JP6") (pin "10") (pinfunction "10_10") (pintype "passive"))
      (node (ref "U$3") (pin "P$44") (pinfunction "44_P$44") (pintype "passive"))
    )
    (net (code "102") (name "Net-(U$4-11)") (class "Default")
      (node (ref "JP6") (pin "11") (pinfunction "11_11") (pintype "passive"))
      (node (ref "U$4") (pin "P$11") (pinfunction "11_P$11") (pintype "passive"))
    )
    (net (code "103") (name "Net-(U$4-22)") (class "Default")
      (node (ref "JP6") (pin "13") (pinfunction "13_13") (pintype "passive"))
      (node (ref "U$4") (pin "P$22") (pinfunction "22_P$22") (pintype "passive"))
    )
    (net (code "104") (name "Net-(U$4-33)") (class "Default")
      (node (ref "JP6") (pin "12") (pinfunction "12_12") (pintype "passive"))
      (node (ref "U$4") (pin "P$33") (pinfunction "33_P$33") (pintype "passive"))
    )
    (net (code "105") (name "Net-(U$23-PH1)") (class "Default")
      (node (ref "R3") (pin "2") (pinfunction "2_2") (pintype "passive"))
      (node (ref "U$23") (pin "6") (pinfunction "PH1_6") (pintype "bidirectional"))
    )
    (net (code "106") (name "unconnected-(JP1-Pad3)") (class "Default")
      (node (ref "JP1") (pin "3") (pinfunction "3_3") (pintype "passive"))
    )
    (net (code "107") (name "unconnected-(JP6-Pad29)") (class "Default")
      (node (ref "JP6") (pin "29") (pinfunction "29_29") (pintype "passive"))
    )
    (net (code "108") (name "unconnected-(JP7-Pad6)") (class "Default")
      (node (ref "JP7") (pin "6") (pinfunction "6_6") (pintype "passive"))
    )
    (net (code "109") (name "unconnected-(JP8-Pad6)") (class "Default")
      (node (ref "JP8") (pin "6") (pinfunction "6_6") (pintype "passive"))
    )
    (net (code "110") (name "unconnected-(R2-E-Pad3)") (class "Default")
      (node (ref "R2") (pin "3") (pinfunction "E_3") (pintype "passive"))
    )
    (net (code "111") (name "unconnected-(U$4-1-PadP$1)") (class "Default")
      (node (ref "U$4") (pin "P$1") (pinfunction "1_P$1") (pintype "passive"))
    )
    (net (code "112") (name "unconnected-(U$4-4-PadP$4)") (class "Default")
      (node (ref "U$4") (pin "P$4") (pinfunction "4_P$4") (pintype "passive"))
    )
    (net (code "113") (name "unconnected-(U$4-44-PadP$44)") (class "Default")
      (node (ref "U$4") (pin "P$44") (pinfunction "44_P$44") (pintype "passive"))
    )
    (net (code "114") (name "unconnected-(U$24-PadA0)") (class "Default")
      (node (ref "U$24") (pin "A0") (pinfunction "A0_A0") (pintype "bidirectional"))
    )
    (net (code "115") (name "unconnected-(U$24-PadCLK)") (class "Default")
      (node (ref "U$24") (pin "CLK") (pinfunction "CLK_CLK") (pintype "bidirectional"))
    )
    (net (code "116") (name "unconnected-(U$24-PadCMD)") (class "Default")
      (node (ref "U$24") (pin "CMD") (pinfunction "CMD_CMD") (pintype "bidirectional"))
    )
    (net (code "117") (name "unconnected-(U$24-PadD2)") (class "Default")
      (node (ref "U$24") (pin "D2") (pinfunction "D2_D2") (pintype "bidirectional"))
    )
    (net (code "118") (name "unconnected-(U$24-PadD3)") (class "Default")
      (node (ref "U$24") (pin "D3") (pinfunction "D3_D3") (pintype "bidirectional"))
    )
    (net (code "119") (name "unconnected-(U$24-PadD4)") (class "Default")
      (node (ref "U$24") (pin "D4") (pinfunction "D4_D4") (pintype "bidirectional"))
    )
    (net (code "120") (name "unconnected-(U$24-PadEN)") (class "Default")
      (node (ref "U$24") (pin "EN") (pinfunction "EN_EN") (pintype "bidirectional"))
    )
    (net (code "121") (name "unconnected-(U$24-PadRST)") (class "Default")
      (node (ref "U$24") (pin "RST") (pinfunction "RST_RST") (pintype "bidirectional"))
    )
    (net (code "122") (name "unconnected-(U$24-PadRSV)") (class "Default")
      (node (ref "U$24") (pin "RSV") (pinfunction "RSV_RSV") (pintype "bidirectional"))
    )
    (net (code "123") (name "unconnected-(U$24-PadRX)") (class "Default")
      (node (ref "U$24") (pin "RX") (pinfunction "RX_RX") (pintype "bidirectional"))
    )
    (net (code "124") (name "unconnected-(U$24-PadSD0)") (class "Default")
      (node (ref "U$24") (pin "SD0") (pinfunction "SD0_SD0") (pintype "bidirectional"))
    )
    (net (code "125") (name "unconnected-(U$24-PadSD1)") (class "Default")
      (node (ref "U$24") (pin "SD1") (pinfunction "SD1_SD1") (pintype "bidirectional"))
    )
    (net (code "126") (name "unconnected-(U$24-PadSD2)") (class "Default")
      (node (ref "U$24") (pin "SD2") (pinfunction "SD2_SD2") (pintype "bidirectional"))
    )
    (net (code "127") (name "unconnected-(U$24-PadSD3)") (class "Default")
      (node (ref "U$24") (pin "SD3") (pinfunction "SD3_SD3") (pintype "bidirectional"))
    )
    (net (code "128") (name "unconnected-(U$24-PadTX)") (class "Default")
      (node (ref "U$24") (pin "TX") (pinfunction "TX_TX") (pintype "bidirectional"))
    )
    (net (code "129") (name "unconnected-(U$24-RSV-PadRSV@1)") (class "Default")
      (node (ref "U$24") (pin "RSV@1") (pinfunction "RSV_RSV@1") (pintype "bidirectional"))
    )
    (net (code "130") (name "unconnected-(U1-A6-Pad9)") (class "Default")
      (node (ref "U1") (pin "9") (pinfunction "A6_9") (pintype "bidirectional"))
    )
    (net (code "131") (name "unconnected-(U1-A7-Pad10)") (class "Default")
      (node (ref "U1") (pin "10") (pinfunction "A7_10") (pintype "bidirectional"))
    )
    (net (code "132") (name "unconnected-(U1-B6-Pad15)") (class "Default")
      (node (ref "U1") (pin "15") (pinfunction "B6_15") (pintype "bidirectional"))
    )
    (net (code "133") (name "unconnected-(U1-B7-Pad14)") (class "Default")
      (node (ref "U1") (pin "14") (pinfunction "B7_14") (pintype "bidirectional"))
    )
  )
)
